# USB-UART.net
KiCad netlist of a schematic drawn in Altium Designer
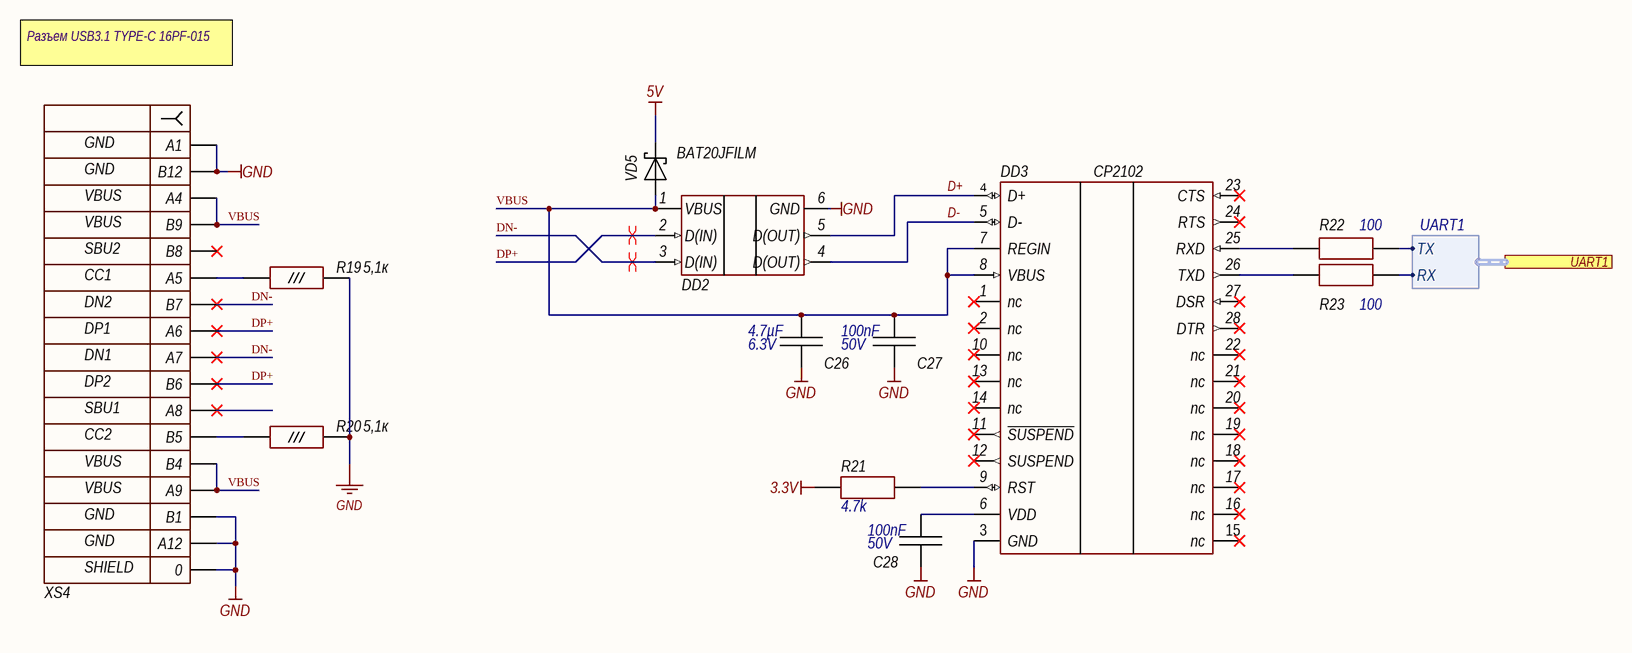
[diagram p0: USB-UART.SchDoc]

(export (version "E")
  (design (tool "Eeschema 10.0.6"))
  (components
    (comp (ref "C26")
      (value "CC0603KRX7R5BB475")
      (footprint "CAPC0603_H0.90_N")
      (description "4.7uF 10% X7R 0603")
      (fields
        (field (name "TOLERANCE") "10%")
        (field (name "VOLTAGE RATING") "6.3V")
        (field (name "MANUFACTURER") "Yageo")
        (field (name "CAPACITANCE") "4.7µF")
        (field (name "AUTHOR") "v.ivanchenko")
      )
      (libsource (lib "EnCata Concord Pro") (part "C"))
    )
    (comp (ref "C27")
      (value "CC0603KRX7R7BB104")
      (footprint "CAPC0603_H0.90_N")
      (description "0.1uF 10% X7R 50V 0603")
      (fields
        (field (name "TOLERANCE") "10%")
        (field (name "CAPACITANCE") "100nF")
        (field (name "VOLTAGE RATING") "50V")
        (field (name "MANUFACTURER") "Yageo")
        (field (name "AUTHOR") "v.ivanchenko")
      )
      (libsource (lib "EnCata Concord Pro") (part "C"))
    )
    (comp (ref "C28")
      (value "CC0603KRX7R7BB104")
      (footprint "CAPC0603_H0.90_N")
      (description "0.1uF 10% X7R 50V 0603")
      (fields
        (field (name "TOLERANCE") "10%")
        (field (name "CAPACITANCE") "100nF")
        (field (name "VOLTAGE RATING") "50V")
        (field (name "MANUFACTURER") "Yageo")
        (field (name "AUTHOR") "v.ivanchenko")
      )
      (libsource (lib "EnCata Concord Pro") (part "C"))
    )
    (comp (ref "DD2")
      (value "STF202-22T1G")
      (footprint "TSOP-6")
      (description "DD STF202-22T1G USB Filter with ESD protection")
      (fields
        (field (name "PARTNUMBER") "STF202-22T1G_ON Semiconductor")
        (field (name "MANUFACTURER") "ON Semiconductor")
        (field (name "АВТОР") "Коваль Максим")
      )
      (libsource (lib "EncataLIB") (part "DD_STF202-22T1G"))
    )
    (comp (ref "DD3")
      (value "CP2102")
      (footprint "QFN50P500X500X90_HS-29N")
      (description "DD CP2102 SINGLE-CHIP USB-TO-UART BRIDGE")
      (fields
        (field (name "PARTNUMBER") "CP2102_Silicon Labs")
        (field (name "MANUFACTURER") "Silicon Labs")
        (field (name "АВТОР") "Касперович Андрей")
      )
      (libsource (lib "EncataLIB") (part "DD_CP2102"))
    )
    (comp (ref "R19")
      (value "5,1к")
      (footprint "RESC0402_N")
      (description "RES 5k1 SMD 0402 1%")
      (fields
        (field (name "PARTNUMBER") "RC0402FR-075K1L_Yageo")
        (field (name "MANUFACTURER") "Yageo")
        (field (name "АВТОР") "Анципов Антон")
      )
      (libsource (lib "EncataLIB") (part "R_0.05W"))
    )
    (comp (ref "R20")
      (value "5,1к")
      (footprint "RESC0402_N")
      (description "RES 5k1 SMD 0402 1%")
      (fields
        (field (name "PARTNUMBER") "RC0402FR-075K1L_Yageo")
        (field (name "MANUFACTURER") "Yageo")
        (field (name "АВТОР") "Анципов Антон")
      )
      (libsource (lib "EncataLIB") (part "R_0.05W"))
    )
    (comp (ref "R21")
      (value "RC0603FR-074K7L")
      (footprint "RESC0603_N")
      (description "RES SMD 4,7 KOHM 1% 1/10W 0603")
      (fields
        (field (name "MANUFACTURER") "Yageo")
        (field (name "RESISTANCE") "4.7k")
        (field (name "TOLERANCE") "1%")
        (field (name "AUTHOR") "M.S. Koval")
      )
      (libsource (lib "EnCata Concord Pro") (part "R_GENERAL"))
    )
    (comp (ref "R22")
      (value "RC0603FR-07100RL")
      (footprint "RESC0603_N")
      (description "RES SMD 100 OHM 1% 1/10W 0603")
      (fields
        (field (name "MANUFACTURER") "Yageo")
        (field (name "RESISTANCE") "100")
        (field (name "TOLERANCE") "1%")
        (field (name "AUTHOR") "M.S. Koval")
      )
      (libsource (lib "EnCata Concord Pro") (part "R_GENERAL"))
    )
    (comp (ref "R23")
      (value "RC0603FR-07100RL")
      (footprint "RESC0603_N")
      (description "RES SMD 100 OHM 1% 1/10W 0603")
      (fields
        (field (name "MANUFACTURER") "Yageo")
        (field (name "RESISTANCE") "100")
        (field (name "TOLERANCE") "1%")
        (field (name "AUTHOR") "M.S. Koval")
      )
      (libsource (lib "EnCata Concord Pro") (part "R_GENERAL"))
    )
    (comp (ref "VD5")
      (value "BAT20JFILM")
      (footprint "SOD-323")
      (description "DIODE SCHOTTKY 23V 1A")
      (fields
        (field (name "PARTNUMBER") "BAT20JFILM_STMicroelectronics")
        (field (name "MANUFACTURER") "STMicroelectronics")
        (field (name "АВТОР") "Селедцов Михаил")
      )
      (libsource (lib "EncataLIB") (part "VD_SCHOTTKY"))
    )
    (comp (ref "XS4")
      (value "16pf-015")
      (footprint "XS_16PF-015")
      (description "USB3.1 TYPEC 16P SMD RA")
      (fields (field (name "MANUFACTURER") "JAE") (field (name "AUTHOR") "V.O.Ivanchenko"))
      (libsource (lib "EnCata Concord Pro") (part "XS_USB_TYPE-C_16PIN_SHIELD"))
    )
  )
  (nets
    (net (code "2") (name "/D+") (class "Default")
      (node (ref "DD2") (pin "5") (pinfunction "D(OUT)_5") (pintype "output"))
      (node (ref "DD3") (pin "4") (pinfunction "D+_4") (pintype "bidirectional"))
    )
    (net (code "3") (name "/D-") (class "Default")
      (node (ref "DD2") (pin "4") (pinfunction "D(OUT)_4") (pintype "output"))
      (node (ref "DD3") (pin "5") (pinfunction "D-_5") (pintype "bidirectional"))
    )
    (net (code "4") (name "/DN-") (class "Default")
      (node (ref "DD2") (pin "3") (pinfunction "D(IN)_3") (pintype "input"))
      (node (ref "XS4") (pin "7") (pinfunction "B7_7") (pintype "passive"))
      (node (ref "XS4") (pin "9") (pinfunction "A7_9") (pintype "passive"))
    )
    (net (code "5") (name "/DP+") (class "Default")
      (node (ref "DD2") (pin "2") (pinfunction "D(IN)_2") (pintype "input"))
      (node (ref "XS4") (pin "10") (pinfunction "B6_10") (pintype "passive"))
      (node (ref "XS4") (pin "8") (pinfunction "A6_8") (pintype "passive"))
    )
    (net (code "6") (name "/RX") (class "Default")
      (node (ref "R23") (pin "2") (pinfunction "2_2") (pintype "passive"))
    )
    (net (code "7") (name "/TX") (class "Default")
      (node (ref "R22") (pin "2") (pinfunction "2_2") (pintype "passive"))
    )
    (net (code "8") (name "/VBUS") (class "Default")
      (node (ref "C26") (pin "1") (pinfunction "1_1") (pintype "passive"))
      (node (ref "C27") (pin "1") (pinfunction "1_1") (pintype "passive"))
      (node (ref "DD2") (pin "1") (pinfunction "VBUS_1") (pintype "power_in"))
      (node (ref "DD3") (pin "7") (pinfunction "REGIN_7") (pintype "power_in"))
      (node (ref "DD3") (pin "8") (pinfunction "VBUS_8") (pintype "input"))
      (node (ref "VD5") (pin "1") (pinfunction "1_1") (pintype "passive"))
      (node (ref "XS4") (pin "13") (pinfunction "B4_13") (pintype "passive"))
      (node (ref "XS4") (pin "14") (pinfunction "A9_14") (pintype "passive"))
      (node (ref "XS4") (pin "3") (pinfunction "A4_3") (pintype "passive"))
      (node (ref "XS4") (pin "4") (pinfunction "B9_4") (pintype "passive"))
    )
    (net (code "10") (name "3.3V") (class "Default")
      (node (ref "R21") (pin "1") (pinfunction "1_1") (pintype "passive"))
    )
    (net (code "11") (name "5V") (class "Default")
      (node (ref "VD5") (pin "2") (pinfunction "2_2") (pintype "passive"))
    )
    (net (code "12") (name "GND") (class "Default")
      (node (ref "C26") (pin "2") (pinfunction "2_2") (pintype "passive"))
      (node (ref "C27") (pin "2") (pinfunction "2_2") (pintype "passive"))
      (node (ref "C28") (pin "2") (pinfunction "2_2") (pintype "passive"))
      (node (ref "DD2") (pin "6") (pinfunction "GND_6") (pintype "power_in"))
      (node (ref "DD3") (pin "3") (pinfunction "GND_3") (pintype "power_in"))
      (node (ref "R19") (pin "2") (pinfunction "2_2") (pintype "passive"))
      (node (ref "R20") (pin "2") (pinfunction "2_2") (pintype "passive"))
      (node (ref "XS4") (pin "0") (pinfunction "0_0") (pintype "passive"))
      (node (ref "XS4") (pin "1") (pinfunction "A1_1") (pintype "passive"))
      (node (ref "XS4") (pin "15") (pinfunction "B1_15") (pintype "passive"))
      (node (ref "XS4") (pin "16") (pinfunction "A12_16") (pintype "passive"))
      (node (ref "XS4") (pin "2") (pinfunction "B12_2") (pintype "passive"))
    )
    (net (code "13") (name "Net-(DD3-RST)") (class "Default")
      (node (ref "DD3") (pin "9") (pinfunction "RST_9") (pintype "bidirectional"))
      (node (ref "R21") (pin "2") (pinfunction "2_2") (pintype "passive"))
    )
    (net (code "14") (name "Net-(DD3-RXD)") (class "Default")
      (node (ref "DD3") (pin "25") (pinfunction "RXD_25") (pintype "input"))
      (node (ref "R22") (pin "1") (pinfunction "1_1") (pintype "passive"))
    )
    (net (code "15") (name "Net-(DD3-TXD)") (class "Default")
      (node (ref "DD3") (pin "26") (pinfunction "TXD_26") (pintype "output"))
      (node (ref "R23") (pin "1") (pinfunction "1_1") (pintype "passive"))
    )
    (net (code "16") (name "Net-(DD3-VDD)") (class "Default")
      (node (ref "C28") (pin "1") (pinfunction "1_1") (pintype "passive"))
      (node (ref "DD3") (pin "6") (pinfunction "VDD_6") (pintype "power_in"))
    )
    (net (code "17") (name "Net-(XS4-A5)") (class "Default")
      (node (ref "R19") (pin "1") (pinfunction "1_1") (pintype "passive"))
      (node (ref "XS4") (pin "6") (pinfunction "A5_6") (pintype "passive"))
    )
    (net (code "18") (name "Net-(XS4-B5)") (class "Default")
      (node (ref "R20") (pin "1") (pinfunction "1_1") (pintype "passive"))
      (node (ref "XS4") (pin "12") (pinfunction "B5_12") (pintype "passive"))
    )
    (net (code "19") (name "unconnected-(DD3-CTS-Pad23)") (class "Default")
      (node (ref "DD3") (pin "23") (pinfunction "CTS_23") (pintype "input+no_connect"))
    )
    (net (code "20") (name "unconnected-(DD3-DSR-Pad27)") (class "Default")
      (node (ref "DD3") (pin "27") (pinfunction "DSR_27") (pintype "input+no_connect"))
    )
    (net (code "21") (name "unconnected-(DD3-DTR-Pad28)") (class "Default")
      (node (ref "DD3") (pin "28") (pinfunction "DTR_28") (pintype "output+no_connect"))
    )
    (net (code "22") (name "unconnected-(DD3-RTS-Pad24)") (class "Default")
      (node (ref "DD3") (pin "24") (pinfunction "RTS_24") (pintype "output+no_connect"))
    )
    (net (code "23") (name "unconnected-(DD3-SUSPEND-Pad12)") (class "Default")
      (node (ref "DD3") (pin "12") (pinfunction "SUSPEND_12") (pintype "output+no_connect"))
    )
    (net (code "24") (name "unconnected-(DD3-nc-Pad1)") (class "Default")
      (node (ref "DD3") (pin "1") (pinfunction "nc_1") (pintype "passive+no_connect"))
    )
    (net (code "25") (name "unconnected-(DD3-nc-Pad2)") (class "Default")
      (node (ref "DD3") (pin "2") (pinfunction "nc_2") (pintype "passive+no_connect"))
    )
    (net (code "26") (name "unconnected-(DD3-nc-Pad10)") (class "Default")
      (node (ref "DD3") (pin "10") (pinfunction "nc_10") (pintype "passive+no_connect"))
    )
    (net (code "27") (name "unconnected-(DD3-nc-Pad13)") (class "Default")
      (node (ref "DD3") (pin "13") (pinfunction "nc_13") (pintype "passive+no_connect"))
    )
    (net (code "28") (name "unconnected-(DD3-nc-Pad14)") (class "Default")
      (node (ref "DD3") (pin "14") (pinfunction "nc_14") (pintype "passive+no_connect"))
    )
    (net (code "29") (name "unconnected-(DD3-nc-Pad15)") (class "Default")
      (node (ref "DD3") (pin "15") (pinfunction "nc_15") (pintype "passive+no_connect"))
    )
    (net (code "30") (name "unconnected-(DD3-nc-Pad16)") (class "Default")
      (node (ref "DD3") (pin "16") (pinfunction "nc_16") (pintype "passive+no_connect"))
    )
    (net (code "31") (name "unconnected-(DD3-nc-Pad17)") (class "Default")
      (node (ref "DD3") (pin "17") (pinfunction "nc_17") (pintype "passive+no_connect"))
    )
    (net (code "32") (name "unconnected-(DD3-nc-Pad18)") (class "Default")
      (node (ref "DD3") (pin "18") (pinfunction "nc_18") (pintype "passive+no_connect"))
    )
    (net (code "33") (name "unconnected-(DD3-nc-Pad19)") (class "Default")
      (node (ref "DD3") (pin "19") (pinfunction "nc_19") (pintype "passive+no_connect"))
    )
    (net (code "34") (name "unconnected-(DD3-nc-Pad20)") (class "Default")
      (node (ref "DD3") (pin "20") (pinfunction "nc_20") (pintype "passive+no_connect"))
    )
    (net (code "35") (name "unconnected-(DD3-nc-Pad21)") (class "Default")
      (node (ref "DD3") (pin "21") (pinfunction "nc_21") (pintype "passive+no_connect"))
    )
    (net (code "36") (name "unconnected-(DD3-nc-Pad22)") (class "Default")
      (node (ref "DD3") (pin "22") (pinfunction "nc_22") (pintype "passive+no_connect"))
    )
    (net (code "37") (name "unconnected-(DD3-~{SUSPEND}-Pad11)") (class "Default")
      (node (ref "DD3") (pin "11") (pinfunction "~{SUSPEND}_11") (pintype "output+no_connect"))
    )
    (net (code "38") (name "unconnected-(XS4-A8-Pad11)") (class "Default")
      (node (ref "XS4") (pin "11") (pinfunction "A8_11") (pintype "passive+no_connect"))
    )
    (net (code "39") (name "unconnected-(XS4-B8-Pad5)") (class "Default")
      (node (ref "XS4") (pin "5") (pinfunction "B8_5") (pintype "passive+no_connect"))
    )
  )
)
